# control3_MCU.net
KiCad netlist of a schematic drawn in Altium Designer
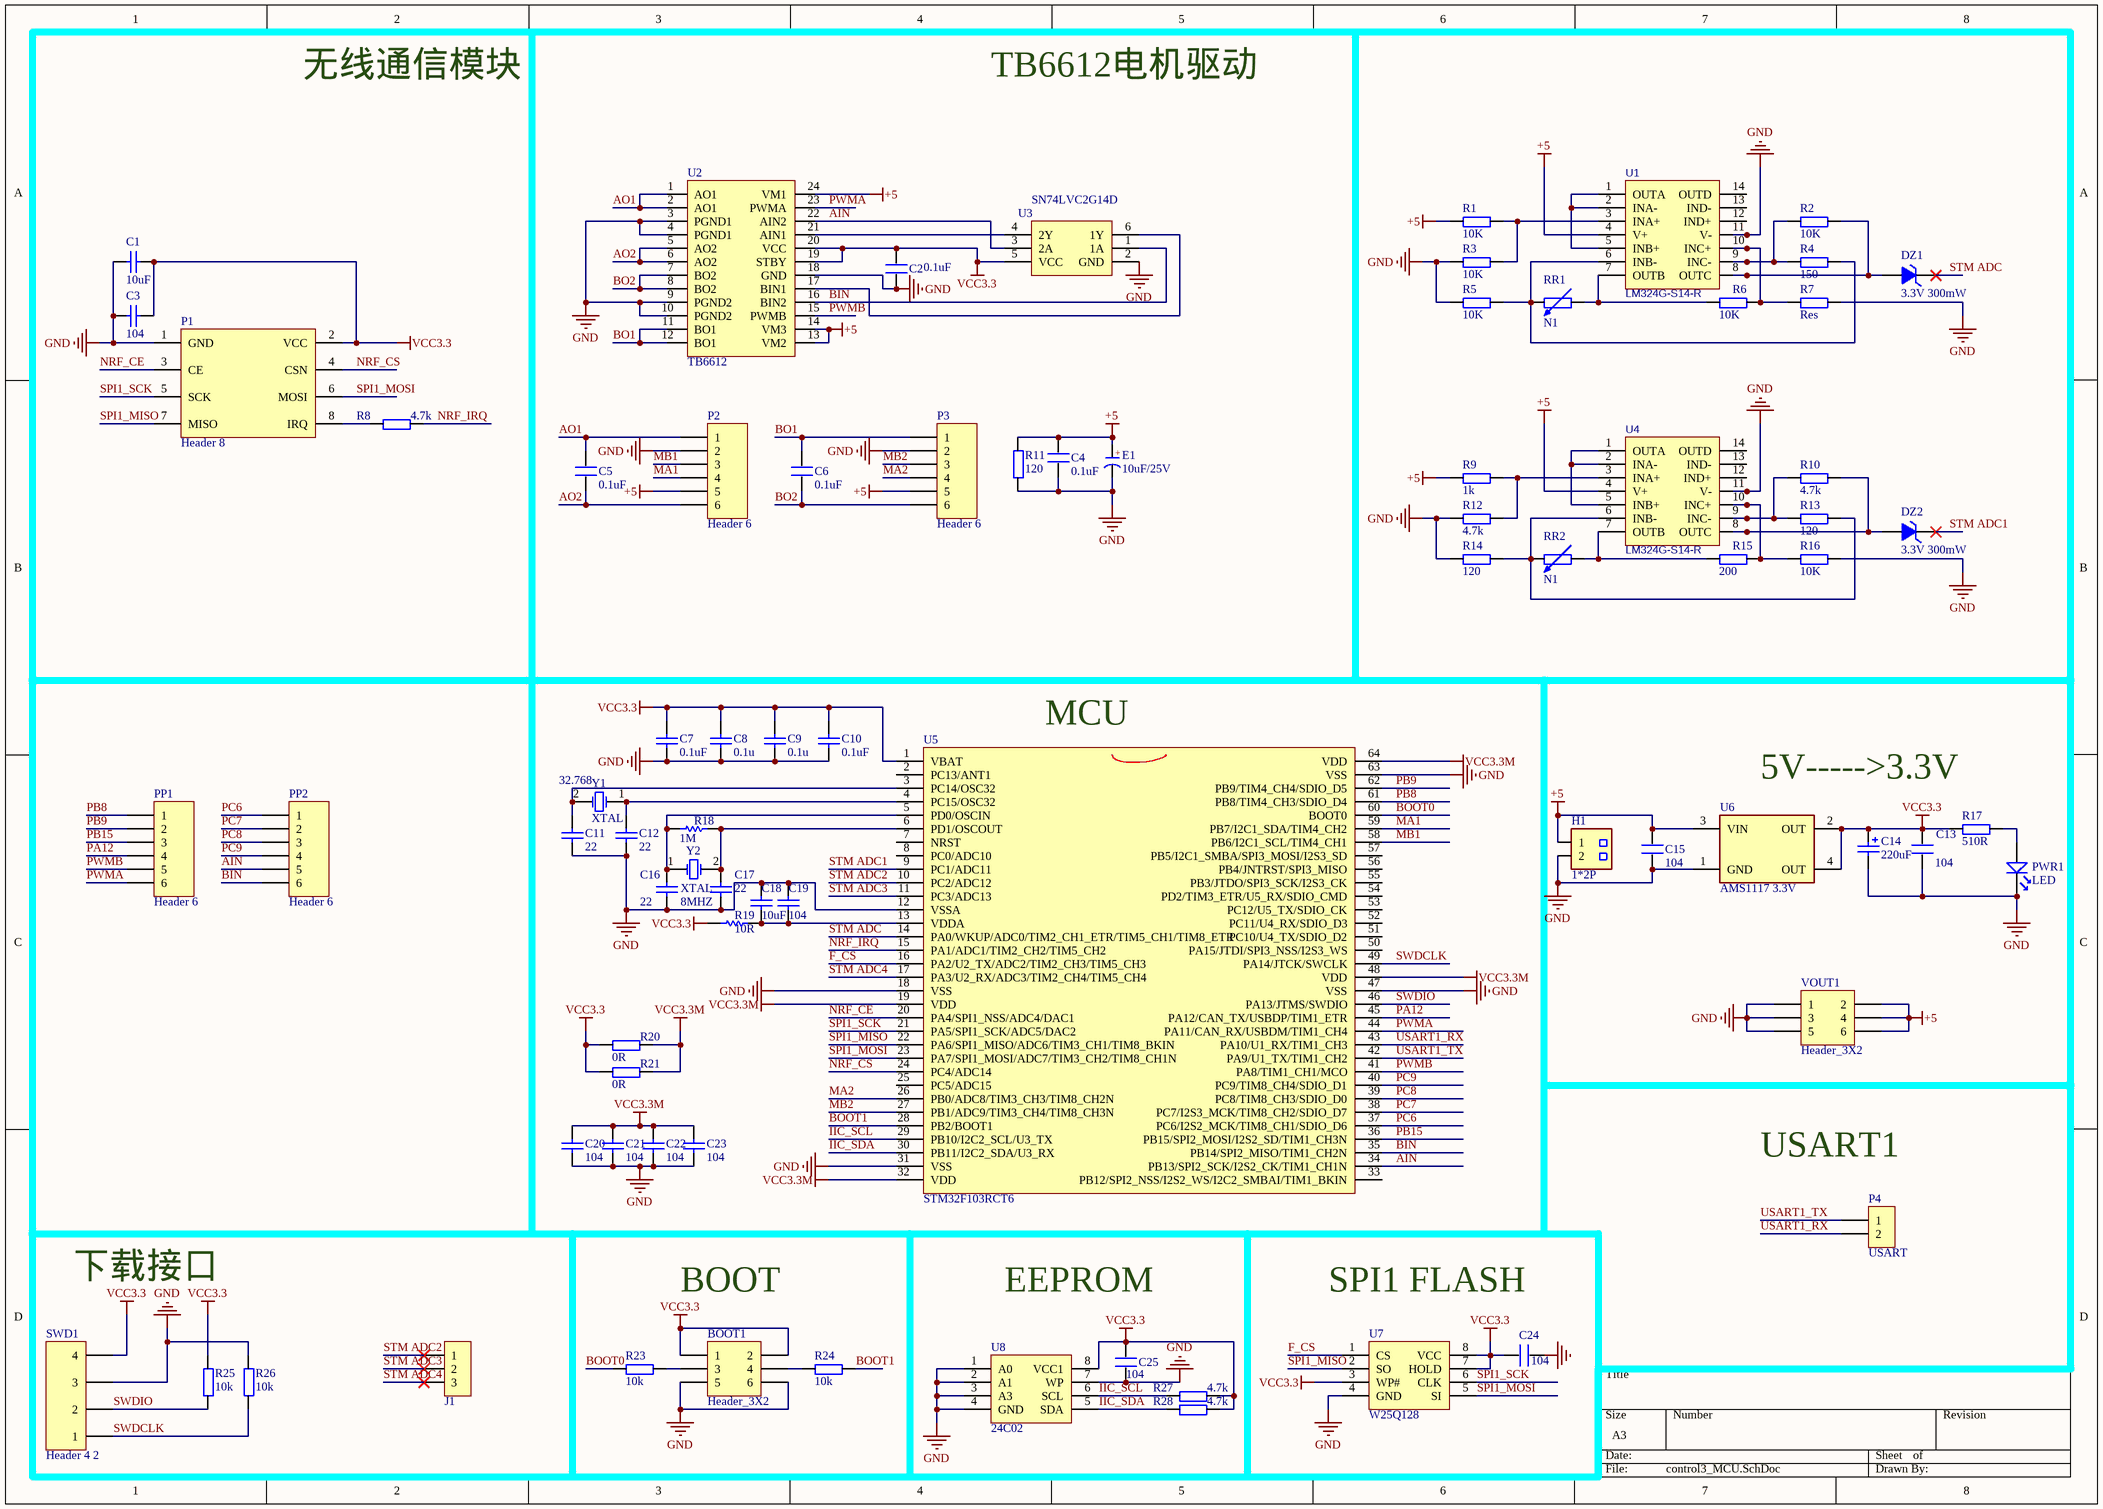
[diagram p0: control3_MCU.SchDoc]

(export (version "E")
  (design (tool "Eeschema 10.0.6"))
  (components
    (comp (ref "BOOT1")
      (value "Header_3X2")
      (footprint "H2.54-2X3")
      (description "Header, 3-Pin, Dual row")
      (libsource (lib "control") (part "Header_3X2"))
    )
    (comp (ref "C1")
      (value "Cap")
      (footprint "CAP[0603]")
      (description "10uF")
      (fields (field (name "ALTIUM_UNNAMED_1") "10uF"))
      (libsource (lib "Sean") (part "Cap"))
    )
    (comp (ref "C2") (value "0.1uF") (footprint "CAP[0603]") (libsource (lib "control") (part "C 0603_L")))
    (comp (ref "C3")
      (value "Cap")
      (footprint "CAP[0603]")
      (description "104")
      (fields (field (name "ALTIUM_UNNAMED_1") "104"))
      (libsource (lib "Sean") (part "Cap"))
    )
    (comp (ref "C4") (value "0.1uF") (footprint "CAP[0603]") (libsource (lib "control") (part "C 0603_L")))
    (comp (ref "C5") (value "0.1uF") (footprint "CAP[0603]") (libsource (lib "control") (part "C 0603_L")))
    (comp (ref "C6") (value "0.1uF") (footprint "CAP[0603]") (libsource (lib "control") (part "C 0603_L")))
    (comp (ref "C7")
      (value "0.1uF")
      (footprint "CAP[0603]")
      (fields (field (name "ALTIUM_UNNAMED_1") "0.1uF"))
      (libsource (lib "Sean") (part "Cap"))
    )
    (comp (ref "C8")
      (value "104")
      (footprint "CAP[0603]")
      (description "0.1uF")
      (fields (field (name "ALTIUM_UNNAMED_1") "0.1u"))
      (libsource (lib "Sean") (part "Cap"))
    )
    (comp (ref "C9")
      (value "104")
      (footprint "CAP[0603]")
      (description "0.1uF")
      (fields (field (name "ALTIUM_UNNAMED_1") "0.1u"))
      (libsource (lib "Sean") (part "Cap"))
    )
    (comp (ref "C10")
      (value "0.1uF")
      (footprint "CAP[0603]")
      (fields (field (name "ALTIUM_UNNAMED_1") "0.1uF"))
      (libsource (lib "Sean") (part "Cap"))
    )
    (comp (ref "C11")
      (value "Cap")
      (footprint "CAP[0603]")
      (description "22")
      (fields (field (name "ALTIUM_UNNAMED_1") "22"))
      (libsource (lib "Sean") (part "Cap"))
    )
    (comp (ref "C12")
      (value "Cap")
      (footprint "CAP[0603]")
      (description "22")
      (fields (field (name "ALTIUM_UNNAMED_1") "22"))
      (libsource (lib "Sean") (part "Cap"))
    )
    (comp (ref "C13") (value "104") (footprint "CAP[0805]") (libsource (lib "control") (part "C 0603_L")))
    (comp (ref "C14") (value "220uF") (footprint "CAP-D8SMD") (libsource (lib "control") (part "CAP+")))
    (comp (ref "C15") (value "104") (footprint "CAP[0805]") (libsource (lib "control") (part "C 0603_L")))
    (comp (ref "C16")
      (value "Cap")
      (footprint "CAP[0805]")
      (description "22")
      (fields (field (name "ALTIUM_UNNAMED_1") "22"))
      (libsource (lib "Sean") (part "Cap"))
    )
    (comp (ref "C17")
      (value "Cap")
      (footprint "CAP[0805]")
      (description "22")
      (fields (field (name "ALTIUM_UNNAMED_1") "22"))
      (libsource (lib "Sean") (part "Cap"))
    )
    (comp (ref "C18")
      (value "Cap")
      (footprint "CAP[0805]")
      (description "10uF")
      (fields (field (name "ALTIUM_UNNAMED_1") "10uF"))
      (libsource (lib "Sean") (part "Cap"))
    )
    (comp (ref "C19")
      (value "Cap")
      (footprint "CAP[0805]")
      (fields (field (name "ALTIUM_UNNAMED_1") "104"))
      (libsource (lib "Sean") (part "Cap"))
    )
    (comp (ref "C20")
      (value "Cap")
      (footprint "CAP[0603]")
      (fields (field (name "ALTIUM_UNNAMED_1") "104"))
      (libsource (lib "Sean") (part "Cap"))
    )
    (comp (ref "C21")
      (value "Cap")
      (footprint "CAP[0603]")
      (fields (field (name "ALTIUM_UNNAMED_1") "104"))
      (libsource (lib "Sean") (part "Cap"))
    )
    (comp (ref "C22")
      (value "Cap")
      (footprint "CAP[0603]")
      (fields (field (name "ALTIUM_UNNAMED_1") "104"))
      (libsource (lib "Sean") (part "Cap"))
    )
    (comp (ref "C23")
      (value "Cap")
      (footprint "CAP[0603]")
      (fields (field (name "ALTIUM_UNNAMED_1") "104"))
      (libsource (lib "Sean") (part "Cap"))
    )
    (comp (ref "C24") (value "104") (footprint "CAP[0603]") (libsource (lib "control") (part "C 0603_L")))
    (comp (ref "C25") (value "104") (footprint "CAP[0603]") (libsource (lib "control") (part "C 0603_L")))
    (comp (ref "DZ1")
      (value "3.3V 300mW")
      (footprint "SOD-123_L2.8-W1.8-LS3.7-RD")
      (description "3V/0.5W稳压管")
      (fields (field (name "版权归属") "源创客"))
      (libsource (lib "control") (part "1N4619"))
    )
    (comp (ref "DZ2")
      (value "3.3V 300mW")
      (footprint "SOD-123_L2.8-W1.8-LS3.7-RD")
      (description "3V/0.5W稳压管")
      (fields (field (name "版权归属") "源创客"))
      (libsource (lib "control") (part "1N4619"))
    )
    (comp (ref "E1")
      (value "10uF/25V")
      (footprint "CAP-SMD_L3.5-W2.8-R-RD")
      (description "直插电解电容")
      (fields (field (name "版权归属") "源创客"))
      (libsource (lib "control") (part "C-CAP"))
    )
    (comp (ref "H1")
      (value "1*2P")
      (footprint "CONN-TH_P2.54_KF128-2.54-2P")
      (libsource (lib "control") (part "HDR1*2"))
    )
    (comp (ref "J1")
      (value "HDR-1X3")
      (footprint "H2.54-1X3")
      (description "3P接插件")
      (fields (field (name "版权归属") "源创客"))
      (libsource (lib "control") (part "Header 3"))
    )
    (comp (ref "P1")
      (value "Header 8")
      (footprint "HDR2.54-LI-2x4P")
      (description "ADC&DAC")
      (libsource (lib "control") (part "Header 8"))
    )
    (comp (ref "P2")
      (value "Header 6")
      (footprint "CONN-TH_6P-P2.54_KF128-2.54-6P")
      (description "motor_Header")
      (libsource (lib "control") (part "Header 6"))
    )
    (comp (ref "P3")
      (value "Header 6")
      (footprint "CONN-TH_6P-P2.54_KF128-2.54-6P")
      (description "motor_Header")
      (libsource (lib "control") (part "Header 6"))
    )
    (comp (ref "P4") (value "USART") (footprint "H2.54-1X2") (libsource (lib "control") (part "Header 2x2")))
    (comp (ref "PP1")
      (value "Header 6")
      (footprint "HDR2.54-LI-6P")
      (description "motor_Header")
      (libsource (lib "control") (part "Header 6"))
    )
    (comp (ref "PP2")
      (value "Header 6")
      (footprint "HDR2.54-LI-6P")
      (description "motor_Header")
      (libsource (lib "control") (part "Header 6"))
    )
    (comp (ref "PWR1") (value "LED") (footprint "LED[0805]") (libsource (lib "control") (part "LED")))
    (comp (ref "R1") (value "10K") (footprint "0603_R_JX") (libsource (lib "ATK-MPU6050六轴传感器模块") (part "R")))
    (comp (ref "R2") (value "10K") (footprint "0603_R_JX") (libsource (lib "ATK-MPU6050六轴传感器模块") (part "R")))
    (comp (ref "R3") (value "10K") (footprint "0603_R_JX") (libsource (lib "ATK-MPU6050六轴传感器模块") (part "R")))
    (comp (ref "R4") (value "150") (footprint "0603_R_JX") (libsource (lib "ATK-MPU6050六轴传感器模块") (part "R")))
    (comp (ref "R5") (value "10K") (footprint "0603_R_JX") (libsource (lib "ATK-MPU6050六轴传感器模块") (part "R")))
    (comp (ref "R6") (value "10K") (footprint "0603_R_JX") (libsource (lib "ATK-MPU6050六轴传感器模块") (part "R")))
    (comp (ref "R7") (value "Res") (footprint "RES[0603]") (libsource (lib "ATK-MPU6050六轴传感器模块") (part "R")))
    (comp (ref "R8")
      (value "4.7k")
      (footprint "RES[0603]")
      (description "电阻")
      (libsource (lib "control") (part "R 0603_L"))
    )
    (comp (ref "R9") (value "1k") (footprint "0603_R_JX") (libsource (lib "ATK-MPU6050六轴传感器模块") (part "R")))
    (comp (ref "R10")
      (value "4.7k")
      (footprint "RES[0603]")
      (libsource (lib "ATK-MPU6050六轴传感器模块") (part "R"))
    )
    (comp (ref "R11") (value "120") (footprint "RES[0603]") (libsource (lib "ATK-MPU6050六轴传感器模块") (part "R")))
    (comp (ref "R12")
      (value "4.7k")
      (footprint "RES[0603]")
      (libsource (lib "ATK-MPU6050六轴传感器模块") (part "R"))
    )
    (comp (ref "R13") (value "120") (footprint "RES[0603]") (libsource (lib "ATK-MPU6050六轴传感器模块") (part "R")))
    (comp (ref "R14") (value "120") (footprint "RES[0603]") (libsource (lib "ATK-MPU6050六轴传感器模块") (part "R")))
    (comp (ref "R15") (value "200") (footprint "0603_R_JX") (libsource (lib "ATK-MPU6050六轴传感器模块") (part "R")))
    (comp (ref "R16") (value "10K") (footprint "0603_R_JX") (libsource (lib "") (part "R_1")))
    (comp (ref "R17")
      (value "510R")
      (footprint "RES[0603]")
      (description "电阻")
      (libsource (lib "control") (part "R 0603_L"))
    )
    (comp (ref "R18")
      (value "Res")
      (footprint "RES[0603]")
      (fields (field (name "ALTIUM_UNNAMED_1") "1M"))
      (libsource (lib "Sean") (part "Res"))
    )
    (comp (ref "R19")
      (value "Res")
      (footprint "RES[0603]")
      (fields (field (name "ALTIUM_UNNAMED_1") "10R"))
      (libsource (lib "Sean") (part "Res"))
    )
    (comp (ref "R20")
      (value "0R")
      (footprint "RES[0603]")
      (description "电阻")
      (libsource (lib "control") (part "R 0603_L"))
    )
    (comp (ref "R21")
      (value "0R")
      (footprint "RES[0603]")
      (description "电阻")
      (libsource (lib "control") (part "R 0603_L"))
    )
    (comp (ref "R23")
      (value "10k")
      (footprint "RES[0603]")
      (description "电阻")
      (libsource (lib "control") (part "R 0603_L"))
    )
    (comp (ref "R24")
      (value "10k")
      (footprint "RES[0603]")
      (description "电阻")
      (libsource (lib "control") (part "R 0603_L"))
    )
    (comp (ref "R25")
      (value "10k")
      (footprint "RES[0603]")
      (description "电阻")
      (libsource (lib "control") (part "R 0603_L"))
    )
    (comp (ref "R26")
      (value "10k")
      (footprint "RES[0603]")
      (description "电阻")
      (libsource (lib "control") (part "R 0603_L"))
    )
    (comp (ref "R27")
      (value "4.7k")
      (footprint "RES[0603]")
      (description "电阻")
      (libsource (lib "control") (part "R 0603_L"))
    )
    (comp (ref "R28")
      (value "4.7k")
      (footprint "RES[0603]")
      (description "电阻")
      (libsource (lib "control") (part "R 0603_L"))
    )
    (comp (ref "RR1")
      (value "N1")
      (footprint "CONN-TH_P2.54_KF128-2.54-2P")
      (description "可变电阻")
      (libsource (lib "control") (part "N1"))
    )
    (comp (ref "RR2")
      (value "N1")
      (footprint "CONN-TH_P2.54_KF128-2.54-2P")
      (description "可变电阻")
      (libsource (lib "control") (part "N1"))
    )
    (comp (ref "SWD1")
      (value "Header 4 2")
      (footprint "H2.54-1X4")
      (description "Header 4")
      (libsource (lib "control") (part "Header 4 2"))
    )
    (comp (ref "U1")
      (value "LM324G-S14-R")
      (footprint "LM324")
      (fields (field (name "BOM_SUPPLIER PART") "C71099"))
      (libsource (lib "control") (part "LM324G-S14-R"))
    )
    (comp (ref "U2") (value "TB6612") (footprint "SSOP24_L") (libsource (lib "TB6612") (part "TB6612")))
    (comp (ref "U3")
      (value "SN74LVC2G14D")
      (footprint "SOT23-6L")
      (description "Header, 3-Pin, Dual row")
      (libsource (lib "control") (part "Header_3X2_1"))
    )
    (comp (ref "U4")
      (value "LM324G-S14-R")
      (footprint "LM324")
      (fields (field (name "BOM_SUPPLIER PART") "C71099"))
      (libsource (lib "control") (part "LM324G-S14-R"))
    )
    (comp (ref "U5")
      (value "STM32F103RCT6")
      (footprint "LQFP-64")
      (libsource (lib "control") (part "STM32F103RCT6"))
    )
    (comp (ref "U6")
      (value "AMS1117 3.3V")
      (footprint "SOT-223(AMS1117-3.3)")
      (libsource (lib "control") (part "AMS1117"))
    )
    (comp (ref "U7") (value "W25Q128") (footprint "SOP-8_width") (libsource (lib "control") (part "W25Q128")))
    (comp (ref "U8")
      (value "24C02")
      (footprint "SO-8")
      (description "EEPROM")
      (libsource (lib "control") (part "24C02"))
    )
    (comp (ref "VOUT1")
      (value "Header_3X2")
      (footprint "H2.54-2X3")
      (description "Header, 3-Pin, Dual row")
      (libsource (lib "control") (part "Header_3X2"))
    )
    (comp (ref "Y1")
      (value "XTAL")
      (footprint "XTAL-32768_2")
      (fields (field (name "ALTIUM_UNNAMED_1") "32.768"))
      (libsource (lib "Sean") (part "XTAL"))
    )
    (comp (ref "Y2")
      (value "XTAL")
      (footprint "XTAL")
      (fields (field (name "ALTIUM_UNNAMED_1") "8MHZ"))
      (libsource (lib "Sean") (part "XTAL"))
    )
  )
  (nets
    (net (code "1") (name "+5") (class "Default")
      (node (ref "C15") (pin "2") (pintype "passive"))
      (node (ref "C4") (pin "2") (pintype "passive"))
      (node (ref "E1") (pin "1") (pinfunction "A_1") (pintype "passive"))
      (node (ref "H1") (pin "1") (pinfunction "1_1") (pintype "passive"))
      (node (ref "P2") (pin "5") (pinfunction "5_5") (pintype "passive"))
      (node (ref "P3") (pin "5") (pinfunction "5_5") (pintype "passive"))
      (node (ref "R1") (pin "1") (pintype "passive"))
      (node (ref "R11") (pin "2") (pintype "passive"))
      (node (ref "R9") (pin "1") (pintype "passive"))
      (node (ref "U1") (pin "4") (pinfunction "V+_4") (pintype "passive"))
      (node (ref "U2") (pin "13") (pinfunction "VM2_13") (pintype "passive"))
      (node (ref "U2") (pin "14") (pinfunction "VM3_14") (pintype "passive"))
      (node (ref "U2") (pin "24") (pinfunction "VM1_24") (pintype "passive"))
      (node (ref "U4") (pin "4") (pinfunction "V+_4") (pintype "passive"))
      (node (ref "U6") (pin "3") (pinfunction "VIN_3") (pintype "passive"))
      (node (ref "VOUT1") (pin "2") (pinfunction "2_2") (pintype "passive"))
      (node (ref "VOUT1") (pin "4") (pinfunction "4_4") (pintype "passive"))
      (node (ref "VOUT1") (pin "6") (pinfunction "6_6") (pintype "passive"))
    )
    (net (code "2") (name "/AIN") (class "Default")
      (node (ref "PP2") (pin "5") (pinfunction "5_5") (pintype "passive"))
      (node (ref "U2") (pin "22") (pinfunction "AIN2_22") (pintype "passive"))
      (node (ref "U3") (pin "3") (pinfunction "2A_3") (pintype "passive"))
      (node (ref "U5") (pin "34") (pinfunction "PB13/SPI2_SCK/I2S2_CK/TIM1_CH1N_34") (pintype "passive"))
    )
    (net (code "3") (name "/AO1") (class "Default")
      (node (ref "C5") (pin "2") (pintype "passive"))
      (node (ref "P2") (pin "1") (pinfunction "1_1") (pintype "passive"))
      (node (ref "U2") (pin "1") (pinfunction "AO1_1") (pintype "passive"))
      (node (ref "U2") (pin "2") (pinfunction "AO1_2") (pintype "passive"))
    )
    (net (code "4") (name "/AO2") (class "Default")
      (node (ref "C5") (pin "1") (pintype "passive"))
      (node (ref "P2") (pin "6") (pinfunction "6_6") (pintype "passive"))
      (node (ref "U2") (pin "5") (pinfunction "AO2_5") (pintype "passive"))
      (node (ref "U2") (pin "6") (pinfunction "AO2_6") (pintype "passive"))
    )
    (net (code "5") (name "/BIN") (class "Default")
      (node (ref "PP2") (pin "6") (pinfunction "6_6") (pintype "passive"))
      (node (ref "U2") (pin "16") (pinfunction "BIN2_16") (pintype "passive"))
      (node (ref "U3") (pin "1") (pinfunction "1A_1") (pintype "passive"))
      (node (ref "U5") (pin "35") (pinfunction "PB14/SPI2_MISO/TIM1_CH2N_35") (pintype "passive"))
    )
    (net (code "6") (name "/BO1") (class "Default")
      (node (ref "C6") (pin "2") (pintype "passive"))
      (node (ref "P3") (pin "1") (pinfunction "1_1") (pintype "passive"))
      (node (ref "U2") (pin "11") (pinfunction "BO1_11") (pintype "passive"))
      (node (ref "U2") (pin "12") (pinfunction "BO1_12") (pintype "passive"))
    )
    (net (code "7") (name "/BO2") (class "Default")
      (node (ref "C6") (pin "1") (pintype "passive"))
      (node (ref "P3") (pin "6") (pinfunction "6_6") (pintype "passive"))
      (node (ref "U2") (pin "7") (pinfunction "BO2_7") (pintype "passive"))
      (node (ref "U2") (pin "8") (pinfunction "BO2_8") (pintype "passive"))
    )
    (net (code "8") (name "/BOOT0") (class "Default")
      (node (ref "R23") (pin "1") (pintype "passive"))
      (node (ref "U5") (pin "60") (pinfunction "BOOT0_60") (pintype "passive"))
    )
    (net (code "9") (name "/BOOT1") (class "Default")
      (node (ref "R24") (pin "2") (pintype "passive"))
      (node (ref "U5") (pin "28") (pinfunction "PB2/BOOT1_28") (pintype "passive"))
    )
    (net (code "10") (name "/F_CS") (class "Default")
      (node (ref "U5") (pin "16") (pinfunction "PA2/U2_TX/ADC2/TIM2_CH3/TIM5_CH3_16") (pintype "passive"))
      (node (ref "U7") (pin "1") (pinfunction "CS_1") (pintype "passive"))
    )
    (net (code "11") (name "/IIC_SCL") (class "Default")
      (node (ref "R27") (pin "1") (pintype "passive"))
      (node (ref "U5") (pin "29") (pinfunction "PB10/I2C2_SCL/U3_TX_29") (pintype "passive"))
      (node (ref "U8") (pin "6") (pinfunction "SCL_6") (pintype "passive"))
    )
    (net (code "12") (name "/IIC_SDA") (class "Default")
      (node (ref "R28") (pin "1") (pintype "passive"))
      (node (ref "U5") (pin "30") (pinfunction "PB11/I2C2_SDA/U3_RX_30") (pintype "passive"))
      (node (ref "U8") (pin "5") (pinfunction "SDA_5") (pintype "passive"))
    )
    (net (code "13") (name "/MA1") (class "Default")
      (node (ref "P2") (pin "4") (pinfunction "4_4") (pintype "passive"))
      (node (ref "U5") (pin "59") (pinfunction "PB7/I2C1_SDA/TIM4_CH2_59") (pintype "passive"))
    )
    (net (code "14") (name "/MA2") (class "Default")
      (node (ref "P3") (pin "4") (pinfunction "4_4") (pintype "passive"))
      (node (ref "U5") (pin "26") (pinfunction "PB0/ADC8/TIM3_CH3/TIM8_CH2N_26") (pintype "passive"))
    )
    (net (code "15") (name "/MB1") (class "Default")
      (node (ref "P2") (pin "3") (pinfunction "3_3") (pintype "passive"))
      (node (ref "U5") (pin "58") (pinfunction "PB6/I2C1_SCL/TIM4_CH1_58") (pintype "passive"))
    )
    (net (code "16") (name "/MB2") (class "Default")
      (node (ref "P3") (pin "3") (pinfunction "3_3") (pintype "passive"))
      (node (ref "U5") (pin "27") (pinfunction "PB1/ADC9/TIM3_CH4/TIM8_CH3N_27") (pintype "passive"))
    )
    (net (code "17") (name "/NRF_CE") (class "Default")
      (node (ref "P1") (pin "3") (pinfunction "CE_3") (pintype "passive"))
      (node (ref "U5") (pin "20") (pinfunction "PA4/SPI1_NSS/ADC4/DAC1_20") (pintype "passive"))
    )
    (net (code "18") (name "/NRF_CS") (class "Default")
      (node (ref "P1") (pin "4") (pinfunction "CSN_4") (pintype "passive"))
      (node (ref "U5") (pin "24") (pinfunction "PC4/ADC14_24") (pintype "passive"))
    )
    (net (code "19") (name "/NRF_IRQ") (class "Default")
      (node (ref "R8") (pin "2") (pintype "passive"))
      (node (ref "U5") (pin "15") (pinfunction "PA1/ADC1/TIM2_CH2/TIM5_CH2_15") (pintype "passive"))
    )
    (net (code "20") (name "/PA12") (class "Default")
      (node (ref "PP1") (pin "4") (pinfunction "4_4") (pintype "passive"))
      (node (ref "U5") (pin "45") (pinfunction "PA12/CAN_TX/USBDP/TIM1_ETR_45") (pintype "passive"))
    )
    (net (code "21") (name "/PB8") (class "Default")
      (node (ref "PP1") (pin "1") (pinfunction "1_1") (pintype "passive"))
      (node (ref "U5") (pin "61") (pinfunction "PB8/TIM4_CH3/SDIO_D4_61") (pintype "passive"))
    )
    (net (code "22") (name "/PB9") (class "Default")
      (node (ref "PP1") (pin "2") (pinfunction "2_2") (pintype "passive"))
      (node (ref "U5") (pin "62") (pinfunction "PB9/TIM4_CH4/SDIO_D5_62") (pintype "passive"))
    )
    (net (code "23") (name "/PB15") (class "Default")
      (node (ref "PP1") (pin "3") (pinfunction "3_3") (pintype "passive"))
      (node (ref "U5") (pin "36") (pinfunction "PB15/SPI2_MOSI/I2S2_SD/TIM1_CH3N_36") (pintype "passive"))
    )
    (net (code "24") (name "/PC6") (class "Default")
      (node (ref "PP2") (pin "1") (pinfunction "1_1") (pintype "passive"))
      (node (ref "U5") (pin "37") (pinfunction "PC6/I2S2_MCK/TIM8_CH1/SDIO_D6_37") (pintype "passive"))
    )
    (net (code "25") (name "/PC7") (class "Default")
      (node (ref "PP2") (pin "2") (pinfunction "2_2") (pintype "passive"))
      (node (ref "U5") (pin "38") (pinfunction "PC7/I2S3_MCK/TIM8_CH2/SDIO_D7_38") (pintype "passive"))
    )
    (net (code "26") (name "/PC8") (class "Default")
      (node (ref "PP2") (pin "3") (pinfunction "3_3") (pintype "passive"))
      (node (ref "U5") (pin "39") (pinfunction "PC8/TIM8_CH3/SDIO_D0_39") (pintype "passive"))
    )
    (net (code "27") (name "/PC9") (class "Default")
      (node (ref "PP2") (pin "4") (pinfunction "4_4") (pintype "passive"))
      (node (ref "U5") (pin "40") (pinfunction "PC9/TIM8_CH4/SDIO_D1_40") (pintype "passive"))
    )
    (net (code "28") (name "/PWMA") (class "Default")
      (node (ref "PP1") (pin "6") (pinfunction "6_6") (pintype "passive"))
      (node (ref "U2") (pin "23") (pinfunction "PWMA_23") (pintype "passive"))
      (node (ref "U5") (pin "44") (pinfunction "PA11/CAN_RX/USBDM/TIM1_CH4_44") (pintype "passive"))
    )
    (net (code "29") (name "/PWMB") (class "Default")
      (node (ref "PP1") (pin "5") (pinfunction "5_5") (pintype "passive"))
      (node (ref "U2") (pin "15") (pinfunction "PWMB_15") (pintype "passive"))
      (node (ref "U5") (pin "41") (pinfunction "PA8/TIM1_CH1/MCO_41") (pintype "passive"))
    )
    (net (code "30") (name "/SPI1_MISO") (class "Default")
      (node (ref "P1") (pin "7") (pinfunction "MISO_7") (pintype "passive"))
      (node (ref "U5") (pin "22") (pinfunction "PA6/SPI1_MISO/ADC6/TIM3_CH1/TIM8_BKIN_22") (pintype "passive"))
      (node (ref "U7") (pin "2") (pinfunction "SO_2") (pintype "passive"))
    )
    (net (code "31") (name "/SPI1_MOSI") (class "Default")
      (node (ref "P1") (pin "6") (pinfunction "MOSI_6") (pintype "passive"))
      (node (ref "U5") (pin "23") (pinfunction "PA7/SPI1_MOSI/ADC7/TIM3_CH2/TIM8_CH1N_23") (pintype "passive"))
      (node (ref "U7") (pin "5") (pinfunction "SI_5") (pintype "passive"))
    )
    (net (code "32") (name "/SPI1_SCK") (class "Default")
      (node (ref "P1") (pin "5") (pinfunction "SCK_5") (pintype "passive"))
      (node (ref "U5") (pin "21") (pinfunction "PA5/SPI1_SCK/ADC5/DAC2_21") (pintype "passive"))
      (node (ref "U7") (pin "6") (pinfunction "CLK_6") (pintype "passive"))
    )
    (net (code "33") (name "/STM ADC") (class "Default")
      (node (ref "DZ1") (pin "2") (pinfunction "K_2") (pintype "passive"))
      (node (ref "U5") (pin "14") (pinfunction "PA0/WKUP/ADC0/TIM2_CH1_ETR/TIM5_CH1/TIM8_ETR_14") (pintype "passive"))
    )
    (net (code "34") (name "/STM ADC1") (class "Default")
      (node (ref "DZ2") (pin "2") (pinfunction "K_2") (pintype "passive"))
      (node (ref "U5") (pin "9") (pinfunction "PC1/ADC11_9") (pintype "passive"))
    )
    (net (code "35") (name "/STM ADC2") (class "Default")
      (node (ref "J1") (pin "1") (pinfunction "1_1") (pintype "passive"))
      (node (ref "U5") (pin "10") (pinfunction "PC2/ADC12_10") (pintype "passive"))
    )
    (net (code "36") (name "/STM ADC3") (class "Default")
      (node (ref "J1") (pin "2") (pinfunction "2_2") (pintype "passive"))
      (node (ref "U5") (pin "11") (pinfunction "PC3/ADC13_11") (pintype "passive"))
    )
    (net (code "37") (name "/STM ADC4") (class "Default")
      (node (ref "J1") (pin "3") (pinfunction "3_3") (pintype "passive"))
      (node (ref "U5") (pin "17") (pinfunction "PA3/U2_RX/ADC3/TIM2_CH4/TIM5_CH4_17") (pintype "passive"))
    )
    (net (code "38") (name "/SWDCLK") (class "Default")
      (node (ref "R26") (pin "1") (pintype "passive"))
      (node (ref "SWD1") (pin "1") (pinfunction "1_1") (pintype "passive"))
      (node (ref "U5") (pin "49") (pinfunction "PA14/JTCK/SWCLK_49") (pintype "passive"))
    )
    (net (code "39") (name "/SWDIO") (class "Default")
      (node (ref "R25") (pin "1") (pintype "passive"))
      (node (ref "SWD1") (pin "2") (pinfunction "2_2") (pintype "passive"))
      (node (ref "U5") (pin "46") (pinfunction "PA13/JTMS/SWDIO_46") (pintype "passive"))
    )
    (net (code "40") (name "/USART1_RX") (class "Default")
      (node (ref "P4") (pin "2") (pinfunction "2_2") (pintype "passive"))
      (node (ref "U5") (pin "43") (pinfunction "PA10/U1_RX/TIM1_CH3_43") (pintype "passive"))
    )
    (net (code "41") (name "/USART1_TX") (class "Default")
      (node (ref "P4") (pin "1") (pinfunction "1_1") (pintype "passive"))
      (node (ref "U5") (pin "42") (pinfunction "PA9/U1_TX/TIM1_CH2_42") (pintype "passive"))
    )
    (net (code "42") (name "GND") (class "Default")
      (node (ref "BOOT1") (pin "5") (pinfunction "5_5") (pintype "passive"))
      (node (ref "BOOT1") (pin "6") (pinfunction "6_6") (pintype "passive"))
      (node (ref "C1") (pin "2") (pinfunction "2_2") (pintype "passive"))
      (node (ref "C10") (pin "1") (pinfunction "1_1") (pintype "passive"))
      (node (ref "C11") (pin "1") (pinfunction "1_1") (pintype "passive"))
      (node (ref "C12") (pin "1") (pinfunction "1_1") (pintype "passive"))
      (node (ref "C13") (pin "1") (pintype "passive"))
      (node (ref "C14") (pin "2") (pinfunction "2_2") (pintype "passive"))
      (node (ref "C15") (pin "1") (pintype "passive"))
      (node (ref "C16") (pin "1") (pinfunction "1_1") (pintype "passive"))
      (node (ref "C17") (pin "1") (pinfunction "1_1") (pintype "passive"))
      (node (ref "C18") (pin "2") (pinfunction "2_2") (pintype "passive"))
      (node (ref "C19") (pin "2") (pinfunction "2_2") (pintype "passive"))
      (node (ref "C2") (pin "1") (pintype "passive"))
      (node (ref "C20") (pin "2") (pinfunction "2_2") (pintype "passive"))
      (node (ref "C21") (pin "2") (pinfunction "2_2") (pintype "passive"))
      (node (ref "C22") (pin "2") (pinfunction "2_2") (pintype "passive"))
      (node (ref "C23") (pin "2") (pinfunction "2_2") (pintype "passive"))
      (node (ref "C24") (pin "1") (pintype "passive"))
      (node (ref "C25") (pin "1") (pintype "passive"))
      (node (ref "C3") (pin "2") (pinfunction "2_2") (pintype "passive"))
      (node (ref "C4") (pin "1") (pintype "passive"))
      (node (ref "C7") (pin "1") (pinfunction "1_1") (pintype "passive"))
      (node (ref "C8") (pin "1") (pinfunction "1_1") (pintype "passive"))
      (node (ref "C9") (pin "1") (pinfunction "1_1") (pintype "passive"))
      (node (ref "E1") (pin "2") (pinfunction "K_2") (pintype "passive"))
      (node (ref "H1") (pin "2") (pinfunction "2_2") (pintype "passive"))
      (node (ref "P1") (pin "1") (pinfunction "GND_1") (pintype "passive"))
      (node (ref "P2") (pin "2") (pinfunction "2_2") (pintype "passive"))
      (node (ref "P3") (pin "2") (pinfunction "2_2") (pintype "passive"))
      (node (ref "PWR1") (pin "2") (pinfunction "2_2") (pintype "passive"))
      (node (ref "R11") (pin "1") (pintype "passive"))
      (node (ref "R12") (pin "1") (pintype "passive"))
      (node (ref "R14") (pin "1") (pintype "passive"))
      (node (ref "R16") (pin "1") (pintype "passive"))
      (node (ref "R26") (pin "2") (pintype "passive"))
      (node (ref "R3") (pin "1") (pintype "passive"))
      (node (ref "R5") (pin "1") (pintype "passive"))
      (node (ref "R7") (pin "2") (pintype "passive"))
      (node (ref "SWD1") (pin "3") (pinfunction "3_3") (pintype "passive"))
      (node (ref "U1") (pin "11") (pinfunction "V-_11") (pintype "passive"))
      (node (ref "U2") (pin "10") (pinfunction "PGND2_10") (pintype "passive"))
      (node (ref "U2") (pin "18") (pinfunction "GND_18") (pintype "passive"))
      (node (ref "U2") (pin "3") (pinfunction "PGND1_3") (pintype "passive"))
      (node (ref "U2") (pin "4") (pinfunction "PGND1_4") (pintype "passive"))
      (node (ref "U2") (pin "9") (pinfunction "PGND2_9") (pintype "passive"))
      (node (ref "U3") (pin "2") (pinfunction "GND_2") (pintype "passive"))
      (node (ref "U4") (pin "11") (pinfunction "V-_11") (pintype "passive"))
      (node (ref "U5") (pin "12") (pinfunction "VSSA_12") (pintype "passive"))
      (node (ref "U5") (pin "18") (pinfunction "VSS_18") (pintype "passive"))
      (node (ref "U5") (pin "31") (pinfunction "VSS_31") (pintype "passive"))
      (node (ref "U5") (pin "47") (pinfunction "VSS_47") (pintype "passive"))
      (node (ref "U5") (pin "63") (pinfunction "VSS_63") (pintype "passive"))
      (node (ref "U6") (pin "1") (pinfunction "GND_1") (pintype "passive"))
      (node (ref "U7") (pin "4") (pinfunction "GND_4") (pintype "passive"))
      (node (ref "U8") (pin "1") (pinfunction "A0_1") (pintype "passive"))
      (node (ref "U8") (pin "2") (pinfunction "A1_2") (pintype "passive"))
      (node (ref "U8") (pin "3") (pinfunction "A3_3") (pintype "passive"))
      (node (ref "U8") (pin "4") (pinfunction "GND_4") (pintype "passive"))
      (node (ref "U8") (pin "7") (pinfunction "WP_7") (pintype "passive"))
      (node (ref "VOUT1") (pin "1") (pinfunction "1_1") (pintype "passive"))
      (node (ref "VOUT1") (pin "3") (pinfunction "3_3") (pintype "passive"))
      (node (ref "VOUT1") (pin "5") (pinfunction "5_5") (pintype "passive"))
    )
    (net (code "43") (name "Net-(BOOT1-Pad3)") (class "Default")
      (node (ref "BOOT1") (pin "3") (pinfunction "3_3") (pintype "passive"))
      (node (ref "R23") (pin "2") (pintype "passive"))
    )
    (net (code "44") (name "Net-(BOOT1-Pad4)") (class "Default")
      (node (ref "BOOT1") (pin "4") (pinfunction "4_4") (pintype "passive"))
      (node (ref "R24") (pin "1") (pintype "passive"))
    )
    (net (code "45") (name "Net-(DZ1-A)") (class "Default")
      (node (ref "DZ1") (pin "1") (pinfunction "A_1") (pintype "passive"))
      (node (ref "R2") (pin "2") (pintype "passive"))
      (node (ref "U1") (pin "8") (pinfunction "OUTC_8") (pintype "passive"))
    )
    (net (code "46") (name "Net-(DZ2-A)") (class "Default")
      (node (ref "DZ2") (pin "1") (pinfunction "A_1") (pintype "passive"))
      (node (ref "R10") (pin "2") (pintype "passive"))
      (node (ref "U4") (pin "8") (pinfunction "OUTC_8") (pintype "passive"))
    )
    (net (code "47") (name "Net-(P1-IRQ)") (class "Default")
      (node (ref "P1") (pin "8") (pinfunction "IRQ_8") (pintype "passive"))
      (node (ref "R8") (pin "1") (pintype "passive"))
    )
    (net (code "48") (name "Net-(PWR1-Pad1)") (class "Default")
      (node (ref "PWR1") (pin "1") (pinfunction "1_1") (pintype "passive"))
      (node (ref "R17") (pin "2") (pintype "passive"))
    )
    (net (code "49") (name "Net-(U1-INA+)") (class "Default")
      (node (ref "R1") (pin "2") (pintype "passive"))
      (node (ref "R3") (pin "2") (pintype "passive"))
      (node (ref "U1") (pin "3") (pinfunction "INA+_3") (pintype "passive"))
    )
    (net (code "50") (name "Net-(U1-INA-)") (class "Default")
      (node (ref "U1") (pin "1") (pinfunction "OUTA_1") (pintype "passive"))
      (node (ref "U1") (pin "2") (pinfunction "INA-_2") (pintype "passive"))
      (node (ref "U1") (pin "5") (pinfunction "INB+_5") (pintype "passive"))
    )
    (net (code "51") (name "Net-(U1-INB-)") (class "Default")
      (node (ref "R4") (pin "2") (pintype "passive"))
      (node (ref "R5") (pin "2") (pintype "passive"))
      (node (ref "RR1") (pin "1") (pintype "passive"))
      (node (ref "U1") (pin "6") (pinfunction "INB-_6") (pintype "passive"))
    )
    (net (code "52") (name "Net-(U1-INC+)") (class "Default")
      (node (ref "R6") (pin "2") (pintype "passive"))
      (node (ref "R7") (pin "1") (pintype "passive"))
      (node (ref "U1") (pin "10") (pinfunction "INC+_10") (pintype "passive"))
    )
    (net (code "53") (name "Net-(U1-INC-)") (class "Default")
      (node (ref "R2") (pin "1") (pintype "passive"))
      (node (ref "R4") (pin "1") (pintype "passive"))
      (node (ref "U1") (pin "9") (pinfunction "INC-_9") (pintype "passive"))
    )
    (net (code "54") (name "Net-(U1-OUTB)") (class "Default")
      (node (ref "R6") (pin "1") (pintype "passive"))
      (node (ref "RR1") (pin "2") (pintype "passive"))
      (node (ref "U1") (pin "7") (pinfunction "OUTB_7") (pintype "passive"))
    )
    (net (code "55") (name "Net-(U2-AIN1)") (class "Default")
      (node (ref "U2") (pin "21") (pinfunction "AIN1_21") (pintype "passive"))
      (node (ref "U3") (pin "4") (pinfunction "2Y_4") (pintype "passive"))
    )
    (net (code "56") (name "Net-(U2-BIN1)") (class "Default")
      (node (ref "U2") (pin "17") (pinfunction "BIN1_17") (pintype "passive"))
      (node (ref "U3") (pin "6") (pinfunction "1Y_6") (pintype "passive"))
    )
    (net (code "57") (name "Net-(U4-INA+)") (class "Default")
      (node (ref "R12") (pin "2") (pintype "passive"))
      (node (ref "R9") (pin "2") (pintype "passive"))
      (node (ref "U4") (pin "3") (pinfunction "INA+_3") (pintype "passive"))
    )
    (net (code "58") (name "Net-(U4-INA-)") (class "Default")
      (node (ref "U4") (pin "1") (pinfunction "OUTA_1") (pintype "passive"))
      (node (ref "U4") (pin "2") (pinfunction "INA-_2") (pintype "passive"))
      (node (ref "U4") (pin "5") (pinfunction "INB+_5") (pintype "passive"))
    )
    (net (code "59") (name "Net-(U4-INB-)") (class "Default")
      (node (ref "R13") (pin "2") (pintype "passive"))
      (node (ref "R14") (pin "2") (pintype "passive"))
      (node (ref "RR2") (pin "1") (pintype "passive"))
      (node (ref "U4") (pin "6") (pinfunction "INB-_6") (pintype "passive"))
    )
    (net (code "60") (name "Net-(U4-INC+)") (class "Default")
      (node (ref "R15") (pin "2") (pintype "passive"))
      (node (ref "R16") (pin "2") (pintype "passive"))
      (node (ref "U4") (pin "10") (pinfunction "INC+_10") (pintype "passive"))
    )
    (net (code "61") (name "Net-(U4-INC-)") (class "Default")
      (node (ref "R10") (pin "1") (pintype "passive"))
      (node (ref "R13") (pin "1") (pintype "passive"))
      (node (ref "U4") (pin "9") (pinfunction "INC-_9") (pintype "passive"))
    )
    (net (code "62") (name "Net-(U4-OUTB)") (class "Default")
      (node (ref "R15") (pin "1") (pintype "passive"))
      (node (ref "RR2") (pin "2") (pintype "passive"))
      (node (ref "U4") (pin "7") (pinfunction "OUTB_7") (pintype "passive"))
    )
    (net (code "63") (name "Net-(U5-PC14{slash}OSC32)") (class "Default")
      (node (ref "C11") (pin "2") (pinfunction "2_2") (pintype "passive"))
      (node (ref "U5") (pin "3") (pinfunction "PC14/OSC32_3") (pintype "passive"))
      (node (ref "Y1") (pin "2") (pinfunction "OSC2_2") (pintype "passive"))
    )
    (net (code "64") (name "Net-(U5-PC15{slash}OSC32)") (class "Default")
      (node (ref "C12") (pin "2") (pinfunction "2_2") (pintype "passive"))
      (node (ref "U5") (pin "4") (pinfunction "PC15/OSC32_4") (pintype "passive"))
      (node (ref "Y1") (pin "1") (pinfunction "OSC1_1") (pintype "passive"))
    )
    (net (code "65") (name "Net-(U5-PD0{slash}OSCIN)") (class "Default")
      (node (ref "C16") (pin "2") (pinfunction "2_2") (pintype "passive"))
      (node (ref "R18") (pin "2") (pinfunction "2_2") (pintype "passive"))
      (node (ref "U5") (pin "5") (pinfunction "PD0/OSCIN_5") (pintype "passive"))
      (node (ref "Y2") (pin "1") (pinfunction "OSC1_1") (pintype "passive"))
    )
    (net (code "66") (name "Net-(U5-PD1{slash}OSCOUT)") (class "Default")
      (node (ref "C17") (pin "2") (pinfunction "2_2") (pintype "passive"))
      (node (ref "R18") (pin "1") (pinfunction "1_1") (pintype "passive"))
      (node (ref "U5") (pin "6") (pinfunction "PD1/OSCOUT_6") (pintype "passive"))
      (node (ref "Y2") (pin "2") (pinfunction "OSC2_2") (pintype "passive"))
    )
    (net (code "67") (name "Net-(U5-VDDA)") (class "Default")
      (node (ref "C18") (pin "1") (pinfunction "1_1") (pintype "passive"))
      (node (ref "C19") (pin "1") (pinfunction "1_1") (pintype "passive"))
      (node (ref "R19") (pin "1") (pinfunction "1_1") (pintype "passive"))
      (node (ref "U5") (pin "13") (pinfunction "VDDA_13") (pintype "passive"))
    )
    (net (code "68") (name "VCC3.3") (class "Default")
      (node (ref "BOOT1") (pin "1") (pinfunction "1_1") (pintype "passive"))
      (node (ref "BOOT1") (pin "2") (pinfunction "2_2") (pintype "passive"))
      (node (ref "C1") (pin "1") (pinfunction "1_1") (pintype "passive"))
      (node (ref "C10") (pin "2") (pinfunction "2_2") (pintype "passive"))
      (node (ref "C13") (pin "2") (pintype "passive"))
      (node (ref "C14") (pin "1") (pinfunction "1_1") (pintype "passive"))
      (node (ref "C2") (pin "2") (pintype "passive"))
      (node (ref "C24") (pin "2") (pintype "passive"))
      (node (ref "C25") (pin "2") (pintype "passive"))
      (node (ref "C3") (pin "1") (pinfunction "1_1") (pintype "passive"))
      (node (ref "C7") (pin "2") (pinfunction "2_2") (pintype "passive"))
      (node (ref "C8") (pin "2") (pinfunction "2_2") (pintype "passive"))
      (node (ref "C9") (pin "2") (pinfunction "2_2") (pintype "passive"))
      (node (ref "P1") (pin "2") (pinfunction "VCC_2") (pintype "passive"))
      (node (ref "R17") (pin "1") (pintype "passive"))
      (node (ref "R19") (pin "2") (pinfunction "2_2") (pintype "passive"))
      (node (ref "R20") (pin "1") (pintype "passive"))
      (node (ref "R21") (pin "1") (pintype "passive"))
      (node (ref "R25") (pin "2") (pintype "passive"))
      (node (ref "R27") (pin "2") (pintype "passive"))
      (node (ref "R28") (pin "2") (pintype "passive"))
      (node (ref "SWD1") (pin "4") (pinfunction "4_4") (pintype "passive"))
      (node (ref "U2") (pin "19") (pinfunction "STBY_19") (pintype "passive"))
      (node (ref "U2") (pin "20") (pinfunction "VCC_20") (pintype "passive"))
      (node (ref "U3") (pin "5") (pinfunction "VCC_5") (pintype "passive"))
      (node (ref "U5") (pin "1") (pinfunction "VBAT_1") (pintype "passive"))
      (node (ref "U6") (pin "2") (pinfunction "OUT_2") (pintype "passive"))
      (node (ref "U6") (pin "4") (pinfunction "OUT_4") (pintype "passive"))
      (node (ref "U7") (pin "3") (pinfunction "WP#_3") (pintype "passive"))
      (node (ref "U7") (pin "7") (pinfunction "HOLD_7") (pintype "passive"))
      (node (ref "U7") (pin "8") (pinfunction "VCC_8") (pintype "passive"))
      (node (ref "U8") (pin "8") (pinfunction "VCC1_8") (pintype "passive"))
    )
    (net (code "69") (name "VCC3.3M") (class "Default")
      (node (ref "C20") (pin "1") (pinfunction "1_1") (pintype "passive"))
      (node (ref "C21") (pin "1") (pinfunction "1_1") (pintype "passive"))
      (node (ref "C22") (pin "1") (pinfunction "1_1") (pintype "passive"))
      (node (ref "C23") (pin "1") (pinfunction "1_1") (pintype "passive"))
      (node (ref "R20") (pin "2") (pintype "passive"))
      (node (ref "R21") (pin "2") (pintype "passive"))
      (node (ref "U5") (pin "19") (pinfunction "VDD_19") (pintype "passive"))
      (node (ref "U5") (pin "32") (pinfunction "VDD_32") (pintype "passive"))
      (node (ref "U5") (pin "48") (pinfunction "VDD_48") (pintype "passive"))
      (node (ref "U5") (pin "64") (pinfunction "VDD_64") (pintype "passive"))
    )
    (net (code "70") (name "unconnected-(U1-IND+-Pad12)") (class "Default")
      (node (ref "U1") (pin "12") (pinfunction "IND+_12") (pintype "passive"))
    )
    (net (code "71") (name "unconnected-(U1-IND--Pad13)") (class "Default")
      (node (ref "U1") (pin "13") (pinfunction "IND-_13") (pintype "passive"))
    )
    (net (code "72") (name "unconnected-(U1-OUTD-Pad14)") (class "Default")
      (node (ref "U1") (pin "14") (pinfunction "OUTD_14") (pintype "passive"))
    )
    (net (code "73") (name "unconnected-(U4-IND+-Pad12)") (class "Default")
      (node (ref "U4") (pin "12") (pinfunction "IND+_12") (pintype "passive"))
    )
    (net (code "74") (name "unconnected-(U4-IND--Pad13)") (class "Default")
      (node (ref "U4") (pin "13") (pinfunction "IND-_13") (pintype "passive"))
    )
    (net (code "75") (name "unconnected-(U4-OUTD-Pad14)") (class "Default")
      (node (ref "U4") (pin "14") (pinfunction "OUTD_14") (pintype "passive"))
    )
    (net (code "76") (name "unconnected-(U5-NRST-Pad7)") (class "Default")
      (node (ref "U5") (pin "7") (pinfunction "NRST_7") (pintype "passive"))
    )
    (net (code "77") (name "unconnected-(U5-PA15{slash}JTDI{slash}SPI3_NSS{slash}I2S3_WS-Pad50)") (class "Default")
      (node (ref "U5") (pin "50") (pinfunction "PA15/JTDI/SPI3_NSS/I2S3_WS_50") (pintype "passive"))
    )
    (net (code "78") (name "unconnected-(U5-PB3{slash}JTDO{slash}SPI3_SCK{slash}I2S3_CK-Pad55)") (class "Default")
      (node (ref "U5") (pin "55") (pinfunction "PB3/JTDO/SPI3_SCK/I2S3_CK_55") (pintype "passive"))
    )
    (net (code "79") (name "unconnected-(U5-PB4{slash}JNTRST{slash}SPI3_MISO-Pad56)") (class "Default")
      (node (ref "U5") (pin "56") (pinfunction "PB4/JNTRST/SPI3_MISO_56") (pintype "passive"))
    )
    (net (code "80") (name "unconnected-(U5-PB5{slash}I2C1_SMBA{slash}SPI3_MOSI{slash}I2S3_SD-Pad57)") (class "Default")
      (node (ref "U5") (pin "57") (pinfunction "PB5/I2C1_SMBA/SPI3_MOSI/I2S3_SD_57") (pintype "passive"))
    )
    (net (code "81") (name "unconnected-(U5-PB12{slash}SPI2_NSS{slash}I2S2_WS{slash}I2C2_SMBAI{slash}TIM1_BKIN-Pad33)") (class "Default")
      (node (ref "U5") (pin "33") (pinfunction "PB12/SPI2_NSS/I2S2_WS/I2C2_SMBAI/TIM1_BKIN_33") (pintype "passive"))
    )
    (net (code "82") (name "unconnected-(U5-PC0{slash}ADC10-Pad8)") (class "Default")
      (node (ref "U5") (pin "8") (pinfunction "PC0/ADC10_8") (pintype "passive"))
    )
    (net (code "83") (name "unconnected-(U5-PC5{slash}ADC15-Pad25)") (class "Default")
      (node (ref "U5") (pin "25") (pinfunction "PC5/ADC15_25") (pintype "passive"))
    )
    (net (code "84") (name "unconnected-(U5-PC10{slash}U4_TX{slash}SDIO_D2-Pad51)") (class "Default")
      (node (ref "U5") (pin "51") (pinfunction "PC10/U4_TX/SDIO_D2_51") (pintype "passive"))
    )
    (net (code "85") (name "unconnected-(U5-PC11{slash}U4_RX{slash}SDIO_D3-Pad52)") (class "Default")
      (node (ref "U5") (pin "52") (pinfunction "PC11/U4_RX/SDIO_D3_52") (pintype "passive"))
    )
    (net (code "86") (name "unconnected-(U5-PC12{slash}U5_TX{slash}SDIO_CK-Pad53)") (class "Default")
      (node (ref "U5") (pin "53") (pinfunction "PC12/U5_TX/SDIO_CK_53") (pintype "passive"))
    )
    (net (code "87") (name "unconnected-(U5-PC13{slash}ANT1-Pad2)") (class "Default")
      (node (ref "U5") (pin "2") (pinfunction "PC13/ANT1_2") (pintype "passive"))
    )
    (net (code "88") (name "unconnected-(U5-PD2{slash}TIM3_ETR{slash}U5_RX{slash}SDIO_CMD-Pad54)") (class "Default")
      (node (ref "U5") (pin "54") (pinfunction "PD2/TIM3_ETR/U5_RX/SDIO_CMD_54") (pintype "passive"))
    )
  )
)
